# CircuitBoard.net
KiCad netlist of a schematic drawn in EAGLE
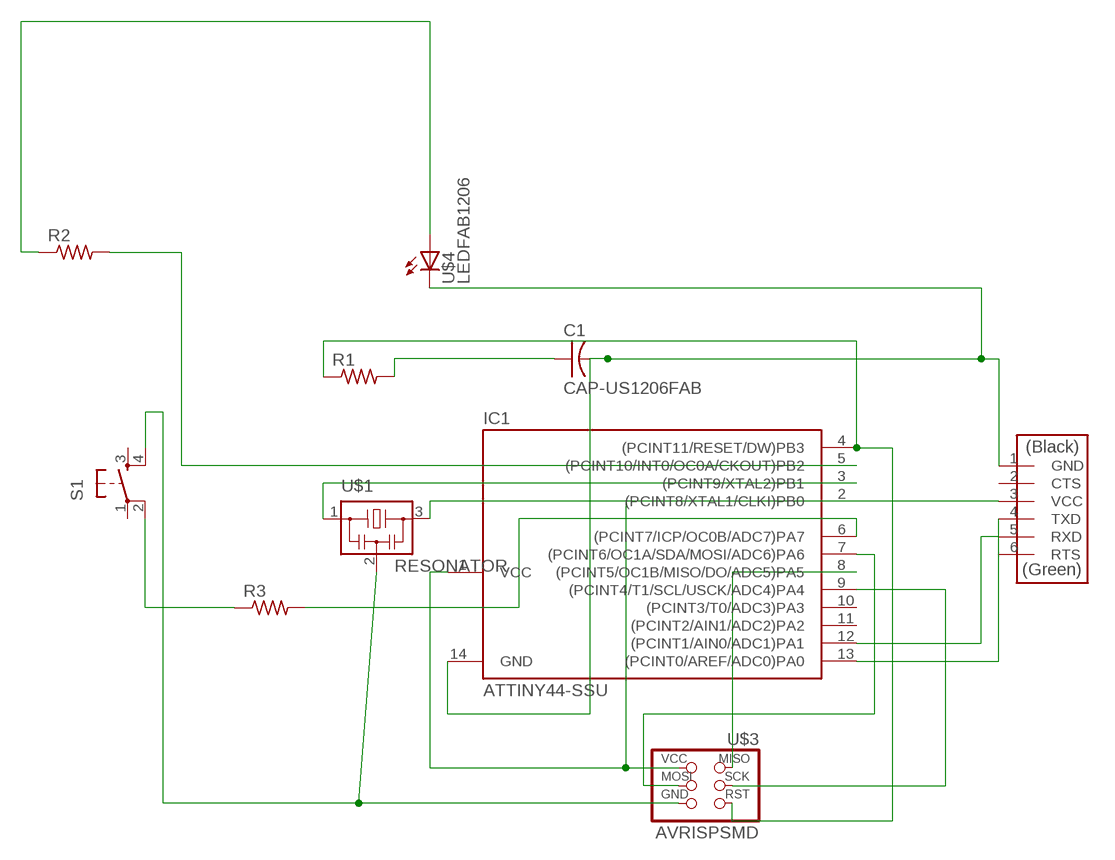
[diagram p0: schematic, sheet 1]

(export (version "E")
  (design (tool "Eeschema 10.0.6"))
  (components
    (comp (ref "C1")
      (value "CAP-US1206FAB")
      (footprint "eagle-import:C1206FAB")
      (libsource (lib "eagle-import") (part "CAP-US1206FAB"))
    )
    (comp (ref "IC1")
      (value "ATTINY44-SSU")
      (footprint "eagle-import:SOIC14")
      (libsource (lib "eagle-import") (part "ATTINY44-SSU"))
    )
    (comp (ref "R1")
      (value "RES-US1206FAB")
      (footprint "eagle-import:R1206FAB")
      (libsource (lib "eagle-import") (part "RES-US1206FAB"))
    )
    (comp (ref "R2")
      (value "RES-US1206FAB")
      (footprint "eagle-import:R1206FAB")
      (libsource (lib "eagle-import") (part "RES-US1206FAB"))
    )
    (comp (ref "R3")
      (value "RES-US1206FAB")
      (footprint "eagle-import:R1206FAB")
      (libsource (lib "eagle-import") (part "RES-US1206FAB"))
    )
    (comp (ref "S1")
      (value "6MM_SWITCH6MM_SWITCH")
      (footprint "eagle-import:6MM_SWITCH")
      (libsource (lib "eagle-import") (part "6MM_SWITCH6MM_SWITCH"))
    )
    (comp (ref "U$1")
      (value "RESONATOR")
      (footprint "eagle-import:EFOBM")
      (libsource (lib "eagle-import") (part "RESONATOR"))
    )
    (comp (ref "U$2")
      (value "FTDI-SMD-HEADER")
      (footprint "eagle-import:1X06SMD")
      (libsource (lib "eagle-import") (part "FTDI-SMD-HEADER"))
    )
    (comp (ref "U$3")
      (value "AVRISPSMD")
      (footprint "eagle-import:2X03SMD")
      (libsource (lib "eagle-import") (part "AVRISPSMD"))
    )
    (comp (ref "U$4")
      (value "LEDFAB1206")
      (footprint "eagle-import:LED1206FAB")
      (libsource (lib "eagle-import") (part "LEDFAB1206"))
    )
  )
  (nets
    (net (code "1") (name "Net-(C1-Pad1)") (class "Default")
      (node (ref "C1") (pin "1") (pinfunction "1_1") (pintype "passive"))
      (node (ref "R1") (pin "2") (pinfunction "2_2") (pintype "passive"))
    )
    (net (code "2") (name "Net-(IC1-(PCINT0{slash}AREF{slash}ADC0)PA0)") (class "Default")
      (node (ref "IC1") (pin "13") (pinfunction "(PCINT0/AREF/ADC0)PA0_13") (pintype "bidirectional"))
      (node (ref "U$2") (pin "4") (pinfunction "TXD_4") (pintype "bidirectional"))
    )
    (net (code "3") (name "Net-(IC1-(PCINT1{slash}AIN0{slash}ADC1)PA1)") (class "Default")
      (node (ref "IC1") (pin "12") (pinfunction "(PCINT1/AIN0/ADC1)PA1_12") (pintype "bidirectional"))
      (node (ref "U$2") (pin "5") (pinfunction "RXD_5") (pintype "bidirectional"))
    )
    (net (code "4") (name "Net-(IC1-(PCINT4{slash}T1{slash}SCL{slash}USCK{slash}ADC4)PA4)") (class "Default")
      (node (ref "IC1") (pin "9") (pinfunction "(PCINT4/T1/SCL/USCK/ADC4)PA4_9") (pintype "bidirectional"))
      (node (ref "U$3") (pin "3") (pinfunction "SCK_3") (pintype "passive"))
    )
    (net (code "5") (name "Net-(IC1-(PCINT5{slash}OC1B{slash}MISO{slash}DO{slash}ADC5)PA5)") (class "Default")
      (node (ref "IC1") (pin "8") (pinfunction "(PCINT5/OC1B/MISO/DO/ADC5)PA5_8") (pintype "bidirectional"))
      (node (ref "U$3") (pin "1") (pinfunction "MISO_1") (pintype "passive"))
    )
    (net (code "6") (name "Net-(IC1-(PCINT6{slash}OC1A{slash}SDA{slash}MOSI{slash}ADC6)PA6)") (class "Default")
      (node (ref "IC1") (pin "7") (pinfunction "(PCINT6/OC1A/SDA/MOSI/ADC6)PA6_7") (pintype "bidirectional"))
      (node (ref "U$3") (pin "4") (pinfunction "MOSI_4") (pintype "passive"))
    )
    (net (code "7") (name "Net-(IC1-(PCINT7{slash}ICP{slash}OC0B{slash}ADC7)PA7)") (class "Default")
      (node (ref "IC1") (pin "6") (pinfunction "(PCINT7/ICP/OC0B/ADC7)PA7_6") (pintype "bidirectional"))
      (node (ref "R3") (pin "2") (pinfunction "2_2") (pintype "passive"))
    )
    (net (code "8") (name "Net-(IC1-(PCINT8{slash}XTAL1{slash}CLKI)PB0)") (class "Default")
      (node (ref "IC1") (pin "2") (pinfunction "(PCINT8/XTAL1/CLKI)PB0_2") (pintype "bidirectional"))
      (node (ref "U$1") (pin "3") (pinfunction "3_3") (pintype "passive"))
    )
    (net (code "9") (name "Net-(IC1-(PCINT9{slash}XTAL2)PB1)") (class "Default")
      (node (ref "IC1") (pin "3") (pinfunction "(PCINT9/XTAL2)PB1_3") (pintype "bidirectional"))
      (node (ref "U$1") (pin "1") (pinfunction "1_1") (pintype "passive"))
    )
    (net (code "10") (name "Net-(IC1-(PCINT10{slash}INT0{slash}OC0A{slash}CKOUT)PB2)") (class "Default")
      (node (ref "IC1") (pin "5") (pinfunction "(PCINT10/INT0/OC0A/CKOUT)PB2_5") (pintype "bidirectional"))
      (node (ref "R2") (pin "2") (pinfunction "2_2") (pintype "passive"))
    )
    (net (code "11") (name "Net-(IC1-(PCINT11{slash}RESET{slash}DW)PB3)") (class "Default")
      (node (ref "IC1") (pin "4") (pinfunction "(PCINT11/RESET/DW)PB3_4") (pintype "bidirectional"))
      (node (ref "R1") (pin "1") (pinfunction "1_1") (pintype "passive"))
      (node (ref "U$3") (pin "5") (pinfunction "RST_5") (pintype "passive"))
    )
    (net (code "12") (name "Net-(IC1-GND)") (class "Default")
      (node (ref "C1") (pin "2") (pinfunction "2_2") (pintype "passive"))
      (node (ref "IC1") (pin "14") (pinfunction "GND_14") (pintype "power_in"))
      (node (ref "U$2") (pin "1") (pinfunction "GND_1") (pintype "bidirectional"))
      (node (ref "U$4") (pin "2") (pinfunction "C_2") (pintype "passive"))
    )
    (net (code "13") (name "Net-(IC1-VCC)") (class "Default")
      (node (ref "IC1") (pin "1") (pinfunction "VCC_1") (pintype "power_in"))
      (node (ref "U$2") (pin "3") (pinfunction "VCC_3") (pintype "bidirectional"))
      (node (ref "U$3") (pin "2") (pinfunction "VCC_2") (pintype "passive"))
    )
    (net (code "14") (name "Net-(S1-P1)") (class "Default")
      (node (ref "R3") (pin "1") (pinfunction "1_1") (pintype "passive"))
      (node (ref "S1") (pin "2") (pinfunction "P1_2") (pintype "passive"))
    )
    (net (code "15") (name "Net-(S1-S1)") (class "Default")
      (node (ref "S1") (pin "4") (pinfunction "S1_4") (pintype "passive"))
      (node (ref "U$1") (pin "2") (pinfunction "2_2") (pintype "passive"))
      (node (ref "U$3") (pin "6") (pinfunction "GND_6") (pintype "passive"))
    )
    (net (code "16") (name "Net-(U$4-A)") (class "Default")
      (node (ref "R2") (pin "1") (pinfunction "1_1") (pintype "passive"))
      (node (ref "U$4") (pin "1") (pinfunction "A_1") (pintype "passive"))
    )
    (net (code "17") (name "unconnected-(IC1-(PCINT2{slash}AIN1{slash}ADC2)PA2-Pad11)") (class "Default")
      (node (ref "IC1") (pin "11") (pinfunction "(PCINT2/AIN1/ADC2)PA2_11") (pintype "bidirectional"))
    )
    (net (code "18") (name "unconnected-(IC1-(PCINT3{slash}T0{slash}ADC3)PA3-Pad10)") (class "Default")
      (node (ref "IC1") (pin "10") (pinfunction "(PCINT3/T0/ADC3)PA3_10") (pintype "bidirectional"))
    )
    (net (code "19") (name "unconnected-(S1-P-Pad1)") (class "Default")
      (node (ref "S1") (pin "1") (pinfunction "P_1") (pintype "passive"))
    )
    (net (code "20") (name "unconnected-(S1-S-Pad3)") (class "Default")
      (node (ref "S1") (pin "3") (pinfunction "S_3") (pintype "passive"))
    )
    (net (code "21") (name "unconnected-(U$2-CTS-Pad2)") (class "Default")
      (node (ref "U$2") (pin "2") (pinfunction "CTS_2") (pintype "bidirectional"))
    )
    (net (code "22") (name "unconnected-(U$2-RTS-Pad6)") (class "Default")
      (node (ref "U$2") (pin "6") (pinfunction "RTS_6") (pintype "bidirectional"))
    )
  )
)
